# TSI-840523.net
KiCad netlist of a schematic drawn in Altium Designer
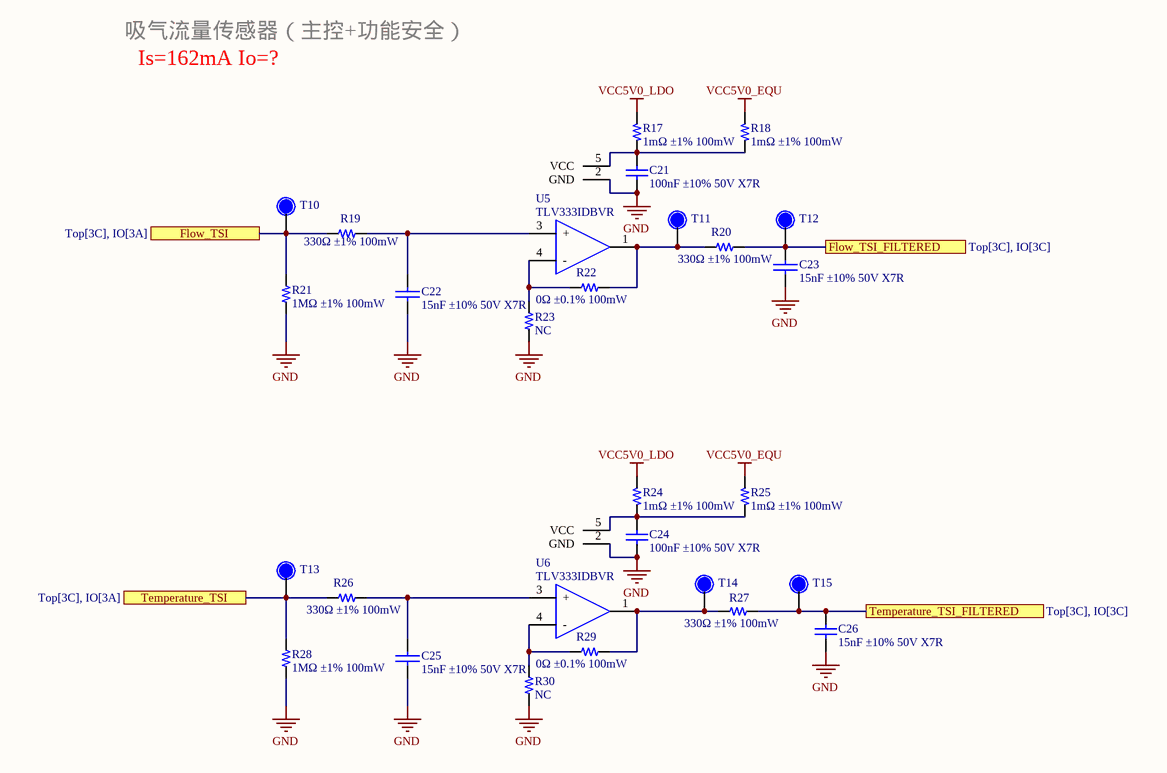
[diagram p0: TSI-840523.SchDoc]

(export (version "E")
  (design (tool "Eeschema 10.0.6"))
  (components
    (comp (ref "C21")
      (value "100nF ±10% 50V X7R")
      (footprint "C-0603")
      (libsource (lib "电容") (part "100nF_1"))
    )
    (comp (ref "C22")
      (value "15nF ±10% 50V X7R")
      (footprint "C-0603")
      (description "Capacitor")
      (libsource (lib "*") (part "CAP"))
    )
    (comp (ref "C23")
      (value "15nF ±10% 50V X7R")
      (footprint "C-0603")
      (description "Capacitor")
      (libsource (lib "*") (part "CAP"))
    )
    (comp (ref "C24")
      (value "100nF ±10% 50V X7R")
      (footprint "C-0603")
      (libsource (lib "电容") (part "100nF_1"))
    )
    (comp (ref "C25")
      (value "15nF ±10% 50V X7R")
      (footprint "C-0603")
      (description "Capacitor")
      (libsource (lib "*") (part "CAP"))
    )
    (comp (ref "C26")
      (value "15nF ±10% 50V X7R")
      (footprint "C-0603")
      (libsource (lib "Device") (part "C-0603"))
    )
    (comp (ref "R17")
      (value "1mΩ ±1% 100mW")
      (footprint "R-0603")
      (description "国巨\r\n1mΩ ±1% 100mW")
      (libsource (lib "电阻") (part "10K_1"))
    )
    (comp (ref "R18")
      (value "1mΩ ±1% 100mW")
      (footprint "R-0603")
      (description "国巨\r\n1mΩ ±1% 100mW")
      (libsource (lib "电阻") (part "10K_1"))
    )
    (comp (ref "R19")
      (value "330Ω ±1% 100mW")
      (footprint "R-0603")
      (description "国巨RC0603FR-07100RL,0603,1/10W")
      (libsource (lib "Device") (part "100R-0603"))
    )
    (comp (ref "R20")
      (value "330Ω ±1% 100mW")
      (footprint "R-0603")
      (description "国巨RC0603FR-07100RL,0603,1/10W")
      (libsource (lib "Device") (part "100R-0603"))
    )
    (comp (ref "R21") (value "1MΩ ±1% 100mW") (footprint "R-0603") (libsource (lib "Device") (part "R-0603")))
    (comp (ref "R22")
      (value "0Ω ±0.1% 100mW")
      (footprint "R-0603")
      (description "国巨RC0805FR-071K")
      (libsource (lib "电阻") (part "1K_1"))
    )
    (comp (ref "R23")
      (value "NC")
      (footprint "R-0603")
      (description "国巨RC0805FR-071K")
      (libsource (lib "电阻") (part "1K_1"))
    )
    (comp (ref "R24")
      (value "1mΩ ±1% 100mW")
      (footprint "R-0603")
      (description "国巨\r\n1mΩ ±1% 100mW")
      (libsource (lib "电阻") (part "10K_1"))
    )
    (comp (ref "R25")
      (value "1mΩ ±1% 100mW")
      (footprint "R-0603")
      (description "国巨\r\n1mΩ ±1% 100mW")
      (libsource (lib "电阻") (part "10K_1"))
    )
    (comp (ref "R26")
      (value "330Ω ±1% 100mW")
      (footprint "R-0603")
      (description "国巨RC0603FR-07100RL,0603,1/10W")
      (libsource (lib "Device") (part "100R-0603"))
    )
    (comp (ref "R27")
      (value "330Ω ±1% 100mW")
      (footprint "R-0603")
      (description "国巨RC0805FR-07100R")
      (libsource (lib "电阻") (part "100Ω_1"))
    )
    (comp (ref "R28") (value "1MΩ ±1% 100mW") (footprint "R-0603") (libsource (lib "Device") (part "R-0603")))
    (comp (ref "R29")
      (value "0Ω ±0.1% 100mW")
      (footprint "R-0603")
      (description "国巨RC0805FR-071K")
      (libsource (lib "电阻") (part "1K_1"))
    )
    (comp (ref "R30")
      (value "NC")
      (footprint "R-0603")
      (description "国巨RC0805FR-071K")
      (libsource (lib "电阻") (part "1K_1"))
    )
    (comp (ref "T10")
      (value "Test?")
      (footprint "TestPad_SMD")
      (description "TestPad_SMD")
      (libsource (lib "Component") (part "TestPad_SMD"))
    )
    (comp (ref "T11")
      (value "Test?")
      (footprint "TestPad_SMD")
      (description "TestPad_SMD")
      (libsource (lib "Component") (part "TestPad_SMD"))
    )
    (comp (ref "T12")
      (value "Test?")
      (footprint "TestPad_SMD")
      (description "TestPad_SMD")
      (libsource (lib "Component") (part "TestPad_SMD"))
    )
    (comp (ref "T13")
      (value "Test?")
      (footprint "TestPad_SMD")
      (description "TestPad_SMD")
      (libsource (lib "Component") (part "TestPad_SMD"))
    )
    (comp (ref "T14")
      (value "Test?")
      (footprint "TestPad_SMD")
      (description "TestPad_SMD")
      (libsource (lib "Component") (part "TestPad_SMD"))
    )
    (comp (ref "T15")
      (value "Test?")
      (footprint "TestPad_SMD")
      (description "TestPad_SMD")
      (libsource (lib "Component") (part "TestPad_SMD"))
    )
    (comp (ref "U5")
      (value "TLV333IDBVR")
      (footprint "SOT23-5")
      (description "品牌：TI，型号：TLV333IDBVR,SOIC-8,–25°~+85°C,单运放，ROHS")
      (libsource (lib "IC") (part "TLV333IDBVR"))
    )
    (comp (ref "U6")
      (value "TLV333IDBVR")
      (footprint "SOT23-5")
      (description "品牌：TI，型号：TLV333IDBVR,SOIC-8,–25°~+85°C,单运放，ROHS")
      (libsource (lib "IC") (part "TLV333IDBVR"))
    )
  )
  (nets
    (net (code "1") (name "/Flow_TSI") (class "Default")
      (node (ref "R19") (pin "1") (pinfunction "TOP_1") (pintype "passive"))
      (node (ref "R21") (pin "1") (pinfunction "1_1") (pintype "passive"))
      (node (ref "T10") (pin "1") (pinfunction "1_1") (pintype "passive"))
    )
    (net (code "2") (name "/Flow_TSI_FILTERED") (class "Default")
      (node (ref "C23") (pin "1") (pinfunction "1_1") (pintype "passive"))
      (node (ref "R20") (pin "2") (pinfunction "BOT_2") (pintype "passive"))
      (node (ref "T12") (pin "1") (pinfunction "1_1") (pintype "passive"))
    )
    (net (code "3") (name "/Temperature_TSI") (class "Default")
      (node (ref "R26") (pin "1") (pinfunction "TOP_1") (pintype "passive"))
      (node (ref "R28") (pin "1") (pinfunction "1_1") (pintype "passive"))
      (node (ref "T13") (pin "1") (pinfunction "1_1") (pintype "passive"))
    )
    (net (code "4") (name "/Temperature_TSI_FILTERED") (class "Default")
      (node (ref "C26") (pin "2") (pinfunction "2_2") (pintype "passive"))
      (node (ref "R27") (pin "1") (pinfunction "TOP_1") (pintype "passive"))
      (node (ref "T15") (pin "1") (pinfunction "1_1") (pintype "passive"))
    )
    (net (code "5") (name "GND") (class "Default")
      (node (ref "C21") (pin "1") (pinfunction "1_1") (pintype "passive"))
      (node (ref "C22") (pin "2") (pinfunction "2_2") (pintype "passive"))
      (node (ref "C23") (pin "2") (pinfunction "2_2") (pintype "passive"))
      (node (ref "C24") (pin "1") (pinfunction "1_1") (pintype "passive"))
      (node (ref "C25") (pin "2") (pinfunction "2_2") (pintype "passive"))
      (node (ref "C26") (pin "1") (pinfunction "1_1") (pintype "passive"))
      (node (ref "R21") (pin "2") (pinfunction "2_2") (pintype "passive"))
      (node (ref "R23") (pin "1") (pinfunction "TOP_1") (pintype "passive"))
      (node (ref "R28") (pin "2") (pinfunction "2_2") (pintype "passive"))
      (node (ref "R30") (pin "1") (pinfunction "TOP_1") (pintype "passive"))
      (node (ref "U5") (pin "2") (pinfunction "GND_2") (pintype "passive"))
      (node (ref "U6") (pin "2") (pinfunction "GND_2") (pintype "passive"))
    )
    (net (code "6") (name "Net-(R17-TOP)") (class "Default")
      (node (ref "C21") (pin "2") (pinfunction "2_2") (pintype "passive"))
      (node (ref "R17") (pin "1") (pinfunction "TOP_1") (pintype "passive"))
      (node (ref "R18") (pin "1") (pinfunction "TOP_1") (pintype "passive"))
      (node (ref "U5") (pin "5") (pinfunction "VCC_5") (pintype "passive"))
    )
    (net (code "7") (name "Net-(R19-BOT)") (class "Default")
      (node (ref "C22") (pin "1") (pinfunction "1_1") (pintype "passive"))
      (node (ref "R19") (pin "2") (pinfunction "BOT_2") (pintype "passive"))
      (node (ref "U5") (pin "3") (pinfunction "+_3") (pintype "passive"))
    )
    (net (code "8") (name "Net-(R20-TOP)") (class "Default")
      (node (ref "R20") (pin "1") (pinfunction "TOP_1") (pintype "passive"))
      (node (ref "R22") (pin "2") (pinfunction "BOT_2") (pintype "passive"))
      (node (ref "T11") (pin "1") (pinfunction "1_1") (pintype "passive"))
      (node (ref "U5") (pin "1") (pintype "passive"))
    )
    (net (code "9") (name "Net-(R22-TOP)") (class "Default")
      (node (ref "R22") (pin "1") (pinfunction "TOP_1") (pintype "passive"))
      (node (ref "R23") (pin "2") (pinfunction "BOT_2") (pintype "passive"))
      (node (ref "U5") (pin "4") (pinfunction "-_4") (pintype "passive"))
    )
    (net (code "10") (name "Net-(R24-TOP)") (class "Default")
      (node (ref "C24") (pin "2") (pinfunction "2_2") (pintype "passive"))
      (node (ref "R24") (pin "1") (pinfunction "TOP_1") (pintype "passive"))
      (node (ref "R25") (pin "1") (pinfunction "TOP_1") (pintype "passive"))
      (node (ref "U6") (pin "5") (pinfunction "VCC_5") (pintype "passive"))
    )
    (net (code "11") (name "Net-(R26-BOT)") (class "Default")
      (node (ref "C25") (pin "1") (pinfunction "1_1") (pintype "passive"))
      (node (ref "R26") (pin "2") (pinfunction "BOT_2") (pintype "passive"))
      (node (ref "U6") (pin "3") (pinfunction "+_3") (pintype "passive"))
    )
    (net (code "12") (name "Net-(R27-BOT)") (class "Default")
      (node (ref "R27") (pin "2") (pinfunction "BOT_2") (pintype "passive"))
      (node (ref "R29") (pin "2") (pinfunction "BOT_2") (pintype "passive"))
      (node (ref "T14") (pin "1") (pinfunction "1_1") (pintype "passive"))
      (node (ref "U6") (pin "1") (pintype "passive"))
    )
    (net (code "13") (name "Net-(R29-TOP)") (class "Default")
      (node (ref "R29") (pin "1") (pinfunction "TOP_1") (pintype "passive"))
      (node (ref "R30") (pin "2") (pinfunction "BOT_2") (pintype "passive"))
      (node (ref "U6") (pin "4") (pinfunction "-_4") (pintype "passive"))
    )
    (net (code "14") (name "VCC5V0_EQU") (class "Default")
      (node (ref "R18") (pin "2") (pinfunction "BOT_2") (pintype "passive"))
      (node (ref "R25") (pin "2") (pinfunction "BOT_2") (pintype "passive"))
    )
    (net (code "15") (name "VCC5V0_LDO") (class "Default")
      (node (ref "R17") (pin "2") (pinfunction "BOT_2") (pintype "passive"))
      (node (ref "R24") (pin "2") (pinfunction "BOT_2") (pintype "passive"))
    )
  )
)
